# Connectors.net
KiCad netlist of a schematic drawn in Altium Designer
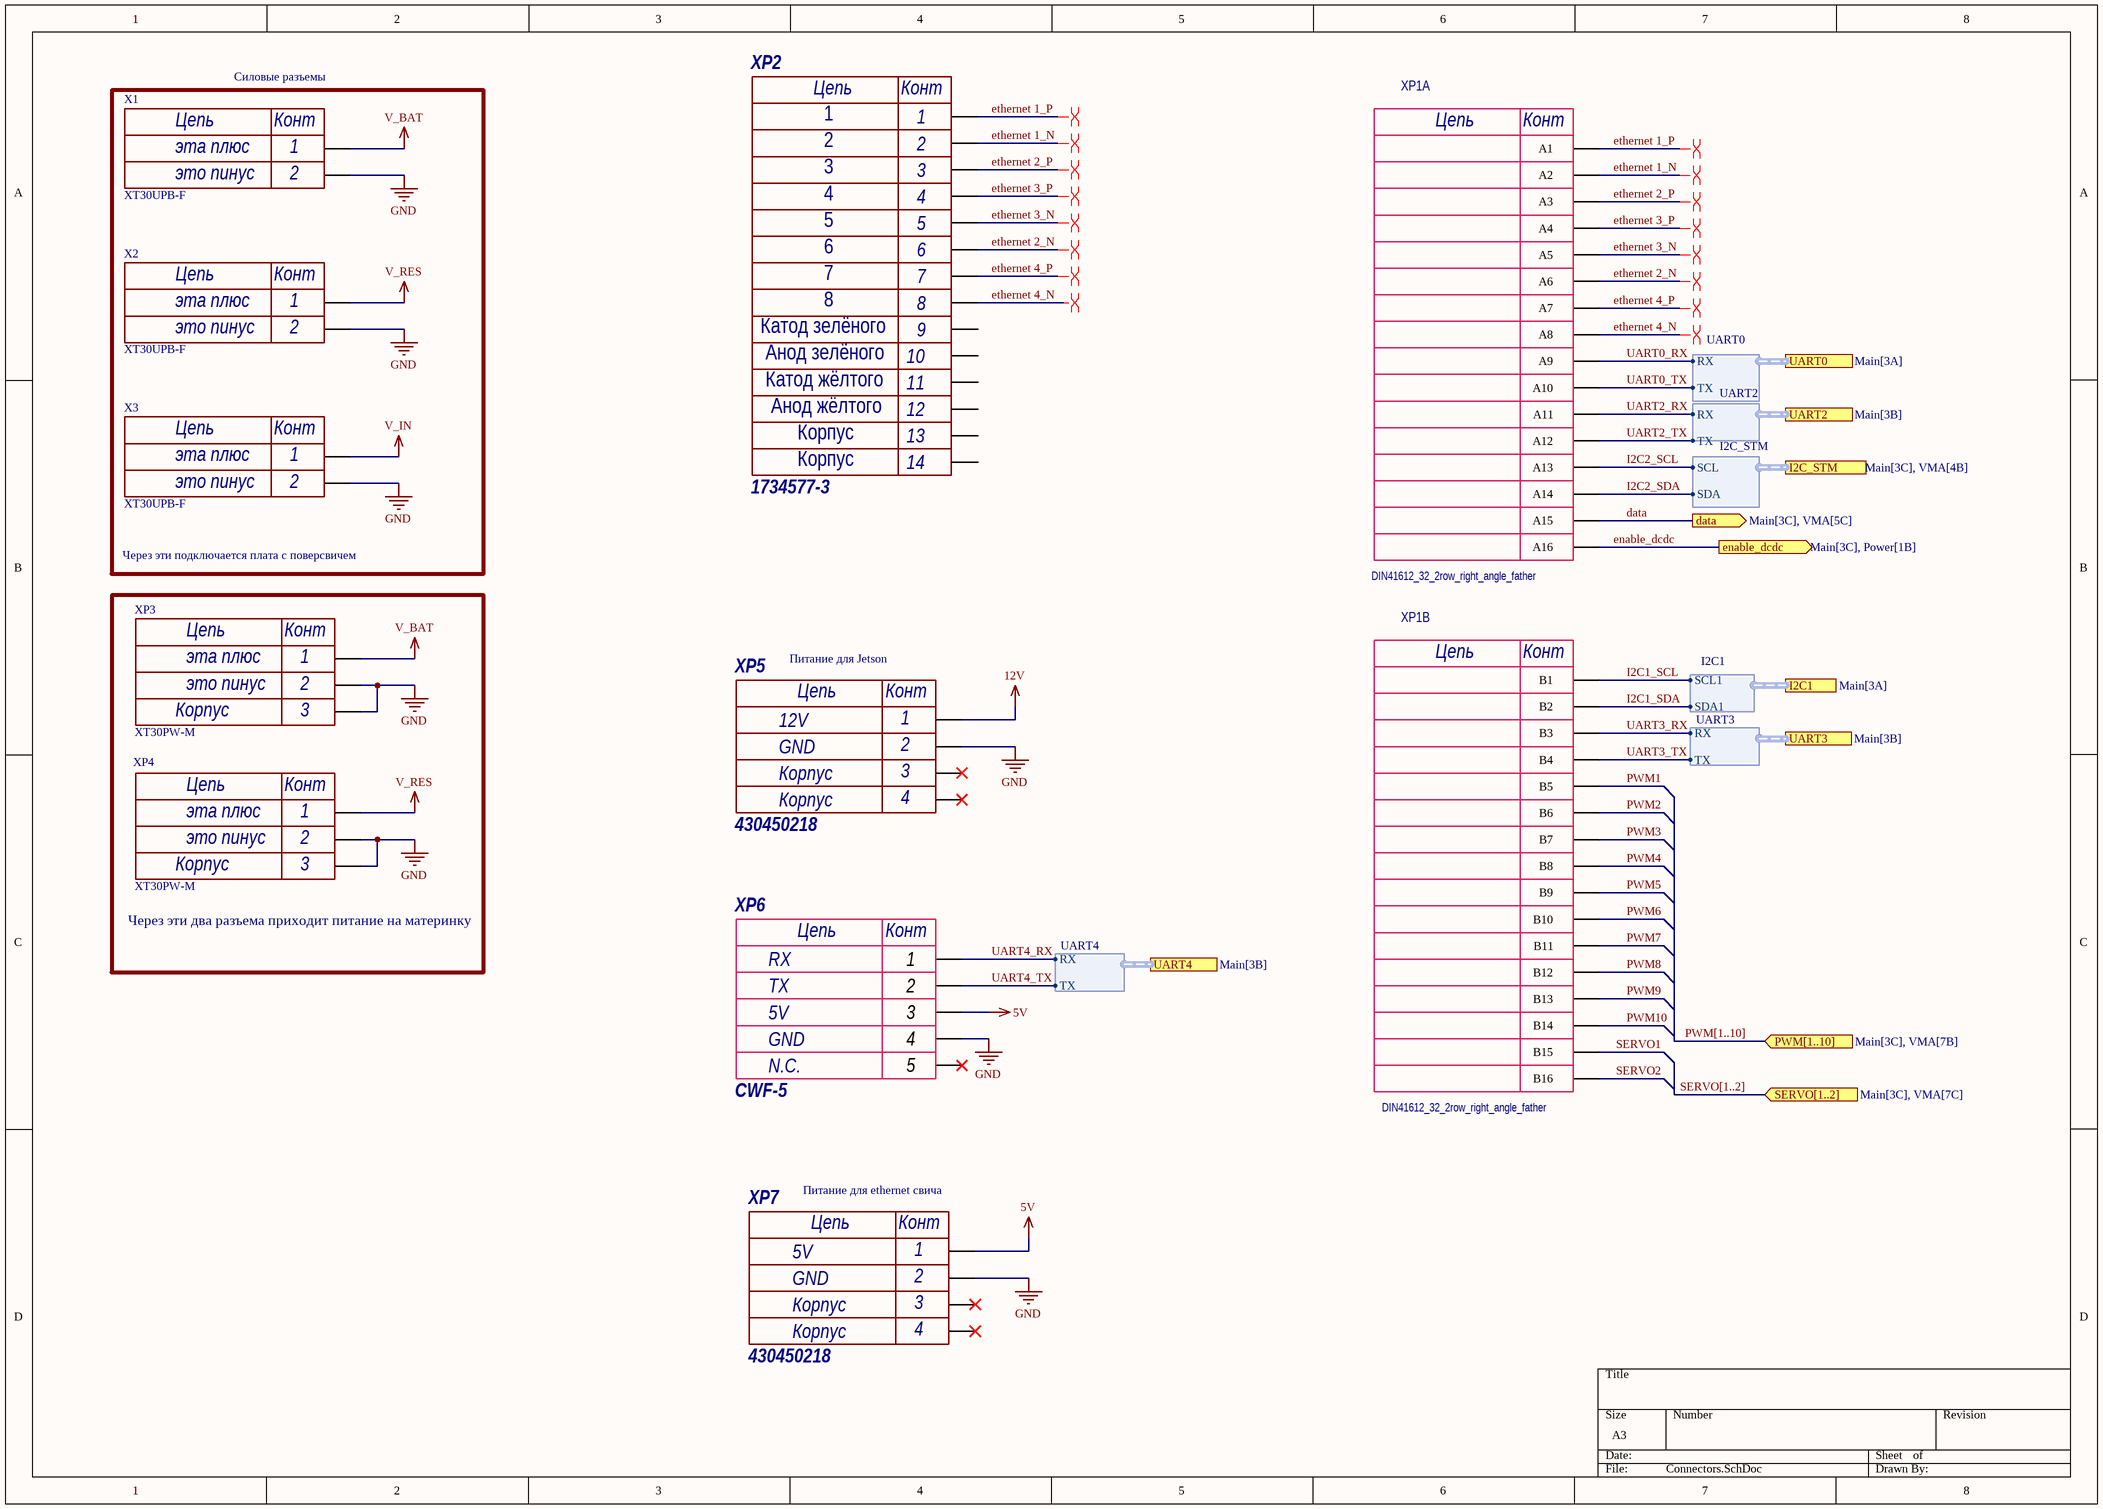
[diagram p0: Connectors.SchDoc]

(export (version "E")
  (design (tool "Eeschema 10.0.6"))
  (components
    (comp (ref "X1")
      (value "XT30UPB-F")
      (footprint "XT30UPB-F")
      (description "30 А (15 продолжительно), прямая мать")
      (fields (field (name "VALUE2") "это пинус") (field (name "VALUE1") "эта плюс"))
      (libsource (lib "Hydrolib") (part "Polar_Conn"))
    )
    (comp (ref "X2")
      (value "XT30UPB-F")
      (footprint "XT30UPB-F")
      (description "30 А (15 продолжительно), прямая мать")
      (fields (field (name "VALUE2") "это пинус") (field (name "VALUE1") "эта плюс"))
      (libsource (lib "Hydrolib") (part "Polar_Conn"))
    )
    (comp (ref "X3")
      (value "XT30UPB-F")
      (footprint "XT30UPB-F")
      (description "30 А (15 продолжительно), прямая мать")
      (fields (field (name "VALUE2") "это пинус") (field (name "VALUE1") "эта плюс"))
      (libsource (lib "Hydrolib") (part "Polar_Conn"))
    )
    (comp (ref "XP1")
      (value "DIN41612_32_2row_right_angle_father")
      (footprint "DIN41612_32_2row_right_angle_father")
      (libsource (lib "") (part "DIN41612_32_2row_1"))
    )
    (comp (ref "XP2")
      (value "1734577-3")
      (footprint "1-1734577-3-rj45-8p8c")
      (description "Модульный разъем, Cat3, RJ45, Гнездо, 8 контакт(-ов), 8 вывод(-ов), 1 порт(-ов)")
      (fields (field (name "PART NUMBER") "1-1734577-3-rj45-8p8c"))
      (libsource (lib "Hydrolib") (part "1-1734577-3-rj45-8p8c"))
    )
    (comp (ref "XP3")
      (value "XT30PW-M")
      (footprint "XT30PW-M")
      (description "30 А (15 продолжительно), 2 контакта разъем угловой отец")
      (fields
        (field (name "VALUE3") "Корпус")
        (field (name "VALUE2") "это пинус")
        (field (name "VALUE1") "эта плюс")
      )
      (libsource (lib "Hydrolib") (part "Polar_Conn_Shield"))
    )
    (comp (ref "XP4")
      (value "XT30PW-M")
      (footprint "XT30PW-M")
      (description "30 А (15 продолжительно), 2 контакта разъем угловой отец")
      (fields
        (field (name "VALUE3") "Корпус")
        (field (name "VALUE2") "это пинус")
        (field (name "VALUE1") "эта плюс")
      )
      (libsource (lib "Hydrolib") (part "Polar_Conn_Shield"))
    )
    (comp (ref "XP5")
      (value "430450218")
      (footprint "Molex_430450218")
      (fields
        (field (name "VALUE3") "Корпус")
        (field (name "VALUE2") "GND")
        (field (name "VALUE4") "Корпус")
        (field (name "VALUE1") "12V")
        (field (name "PART NUMBER") "Molex_430450218")
        (field (name "PARAMETER 1") "Питание для Jetson")
      )
      (libsource (lib "Hydrolib") (part "Molex_430450218"))
    )
    (comp (ref "XP6")
      (value "CWF-5")
      (footprint "CWF-5")
      (description "5-пиновый разъем с ключом")
      (fields
        (field (name "VALUE1") "RX")
        (field (name "VALUE2") "TX")
        (field (name "VALUE3") "5V")
        (field (name "VALUE4") "GND")
        (field (name "VALUE5") "N.C.")
      )
      (libsource (lib "Hydrolib") (part "Conn_5pin"))
    )
    (comp (ref "XP7")
      (value "430450218")
      (footprint "Molex_430450218")
      (fields
        (field (name "VALUE3") "Корпус")
        (field (name "VALUE2") "GND")
        (field (name "VALUE4") "Корпус")
        (field (name "VALUE1") "5V")
        (field (name "PART NUMBER") "Molex_430450218")
        (field (name "PARAMETER 1") "Питание для ethernet свича")
      )
      (libsource (lib "Hydrolib") (part "Molex_430450218"))
    )
  )
  (nets
    (net (code "7") (name "/I2C1_SCL") (class "Default")
      (node (ref "XP1") (pin "B1") (pinfunction "B1_B1") (pintype "passive"))
    )
    (net (code "8") (name "/I2C1_SDA") (class "Default")
      (node (ref "XP1") (pin "B2") (pinfunction "B2_B2") (pintype "passive"))
    )
    (net (code "9") (name "/I2C2_SCL") (class "Default")
      (node (ref "XP1") (pin "A13") (pinfunction "A13_A13") (pintype "passive"))
    )
    (net (code "10") (name "/I2C2_SDA") (class "Default")
      (node (ref "XP1") (pin "A14") (pinfunction "A14_A14") (pintype "passive"))
    )
    (net (code "11") (name "/PWM1") (class "Default")
      (node (ref "XP1") (pin "B5") (pinfunction "B5_B5") (pintype "passive"))
    )
    (net (code "12") (name "/PWM2") (class "Default")
      (node (ref "XP1") (pin "B6") (pinfunction "B6_B6") (pintype "passive"))
    )
    (net (code "13") (name "/PWM3") (class "Default")
      (node (ref "XP1") (pin "B7") (pinfunction "B7_B7") (pintype "passive"))
    )
    (net (code "14") (name "/PWM4") (class "Default")
      (node (ref "XP1") (pin "B8") (pinfunction "B8_B8") (pintype "passive"))
    )
    (net (code "15") (name "/PWM5") (class "Default")
      (node (ref "XP1") (pin "B9") (pinfunction "B9_B9") (pintype "passive"))
    )
    (net (code "16") (name "/PWM6") (class "Default")
      (node (ref "XP1") (pin "B10") (pinfunction "B10_B10") (pintype "passive"))
    )
    (net (code "17") (name "/PWM7") (class "Default")
      (node (ref "XP1") (pin "B11") (pinfunction "B11_B11") (pintype "passive"))
    )
    (net (code "18") (name "/PWM8") (class "Default")
      (node (ref "XP1") (pin "B12") (pinfunction "B12_B12") (pintype "passive"))
    )
    (net (code "19") (name "/PWM9") (class "Default")
      (node (ref "XP1") (pin "B13") (pinfunction "B13_B13") (pintype "passive"))
    )
    (net (code "20") (name "/PWM10") (class "Default")
      (node (ref "XP1") (pin "B14") (pinfunction "B14_B14") (pintype "passive"))
    )
    (net (code "22") (name "/SERVO1") (class "Default")
      (node (ref "XP1") (pin "B15") (pinfunction "B15_B15") (pintype "passive"))
    )
    (net (code "23") (name "/SERVO2") (class "Default")
      (node (ref "XP1") (pin "B16") (pinfunction "B16_B16") (pintype "passive"))
    )
    (net (code "25") (name "/UART0_RX") (class "Default")
      (node (ref "XP1") (pin "A9") (pinfunction "A9_A9") (pintype "passive"))
    )
    (net (code "26") (name "/UART0_TX") (class "Default")
      (node (ref "XP1") (pin "A10") (pinfunction "A10_A10") (pintype "passive"))
    )
    (net (code "27") (name "/UART2_RX") (class "Default")
      (node (ref "XP1") (pin "A11") (pinfunction "A11_A11") (pintype "passive"))
    )
    (net (code "28") (name "/UART2_TX") (class "Default")
      (node (ref "XP1") (pin "A12") (pinfunction "A12_A12") (pintype "passive"))
    )
    (net (code "29") (name "/UART3_RX") (class "Default")
      (node (ref "XP1") (pin "B3") (pinfunction "B3_B3") (pintype "passive"))
    )
    (net (code "30") (name "/UART3_TX") (class "Default")
      (node (ref "XP1") (pin "B4") (pinfunction "B4_B4") (pintype "passive"))
    )
    (net (code "31") (name "/UART4_RX") (class "Default")
      (node (ref "XP6") (pin "1") (pinfunction "1_1") (pintype "passive"))
    )
    (net (code "32") (name "/UART4_TX") (class "Default")
      (node (ref "XP6") (pin "2") (pinfunction "2_2") (pintype "passive"))
    )
    (net (code "33") (name "/data") (class "Default")
      (node (ref "XP1") (pin "A15") (pinfunction "A15_A15") (pintype "passive"))
    )
    (net (code "34") (name "/enable_dcdc") (class "Default")
      (node (ref "XP1") (pin "A16") (pinfunction "A16_A16") (pintype "passive"))
    )
    (net (code "35") (name "/ethernet 1_N") (class "Default")
      (node (ref "XP1") (pin "A2") (pinfunction "A2_A2") (pintype "passive"))
      (node (ref "XP2") (pin "2") (pinfunction "2_2") (pintype "passive"))
    )
    (net (code "36") (name "/ethernet 1_P") (class "Default")
      (node (ref "XP1") (pin "A1") (pinfunction "A1_A1") (pintype "passive"))
      (node (ref "XP2") (pin "1") (pinfunction "1_1") (pintype "passive"))
    )
    (net (code "37") (name "/ethernet 2_N") (class "Default")
      (node (ref "XP1") (pin "A6") (pinfunction "A6_A6") (pintype "passive"))
      (node (ref "XP2") (pin "6") (pinfunction "6_6") (pintype "passive"))
    )
    (net (code "38") (name "/ethernet 2_P") (class "Default")
      (node (ref "XP1") (pin "A3") (pinfunction "A3_A3") (pintype "passive"))
      (node (ref "XP2") (pin "3") (pinfunction "3_3") (pintype "passive"))
    )
    (net (code "39") (name "/ethernet 3_N") (class "Default")
      (node (ref "XP1") (pin "A5") (pinfunction "A5_A5") (pintype "passive"))
      (node (ref "XP2") (pin "5") (pinfunction "5_5") (pintype "passive"))
    )
    (net (code "40") (name "/ethernet 3_P") (class "Default")
      (node (ref "XP1") (pin "A4") (pinfunction "A4_A4") (pintype "passive"))
      (node (ref "XP2") (pin "4") (pinfunction "4_4") (pintype "passive"))
    )
    (net (code "41") (name "/ethernet 4_N") (class "Default")
      (node (ref "XP1") (pin "A8") (pinfunction "A8_A8") (pintype "passive"))
      (node (ref "XP2") (pin "8") (pinfunction "8_8") (pintype "passive"))
    )
    (net (code "42") (name "/ethernet 4_P") (class "Default")
      (node (ref "XP1") (pin "A7") (pinfunction "A7_A7") (pintype "passive"))
      (node (ref "XP2") (pin "7") (pinfunction "7_7") (pintype "passive"))
    )
    (net (code "49") (name "5V") (class "Default")
      (node (ref "XP6") (pin "3") (pinfunction "3_3") (pintype "passive"))
      (node (ref "XP7") (pin "1") (pinfunction "1_1") (pintype "passive"))
    )
    (net (code "50") (name "12V") (class "Default")
      (node (ref "XP5") (pin "1") (pinfunction "1_1") (pintype "passive"))
    )
    (net (code "51") (name "GND") (class "Default")
      (node (ref "X1") (pin "N") (pinfunction "N_N") (pintype "passive"))
      (node (ref "X2") (pin "N") (pinfunction "N_N") (pintype "passive"))
      (node (ref "X3") (pin "N") (pinfunction "N_N") (pintype "passive"))
      (node (ref "XP3") (pin "0") (pinfunction "0_0") (pintype "passive"))
      (node (ref "XP3") (pin "N") (pinfunction "N_N") (pintype "passive"))
      (node (ref "XP4") (pin "0") (pinfunction "0_0") (pintype "passive"))
      (node (ref "XP4") (pin "N") (pinfunction "N_N") (pintype "passive"))
      (node (ref "XP5") (pin "2") (pinfunction "2_2") (pintype "passive"))
      (node (ref "XP6") (pin "4") (pinfunction "4_4") (pintype "passive"))
      (node (ref "XP7") (pin "2") (pinfunction "2_2") (pintype "passive"))
    )
    (net (code "52") (name "V_BAT") (class "Default")
      (node (ref "X1") (pin "P") (pinfunction "P_P") (pintype "passive"))
      (node (ref "XP3") (pin "P") (pinfunction "P_P") (pintype "passive"))
    )
    (net (code "53") (name "V_IN") (class "Default")
      (node (ref "X3") (pin "P") (pinfunction "P_P") (pintype "passive"))
    )
    (net (code "54") (name "V_RES") (class "Default")
      (node (ref "X2") (pin "P") (pinfunction "P_P") (pintype "passive"))
      (node (ref "XP4") (pin "P") (pinfunction "P_P") (pintype "passive"))
    )
    (net (code "55") (name "unconnected-(XP2-Pad9)") (class "Default")
      (node (ref "XP2") (pin "9") (pinfunction "9_9") (pintype "passive"))
    )
    (net (code "56") (name "unconnected-(XP2-Pad10)") (class "Default")
      (node (ref "XP2") (pin "10") (pinfunction "10_10") (pintype "passive"))
    )
    (net (code "57") (name "unconnected-(XP2-Pad11)") (class "Default")
      (node (ref "XP2") (pin "11") (pinfunction "11_11") (pintype "passive"))
    )
    (net (code "58") (name "unconnected-(XP2-Pad12)") (class "Default")
      (node (ref "XP2") (pin "12") (pinfunction "12_12") (pintype "passive"))
    )
    (net (code "59") (name "unconnected-(XP2-PadMH1)") (class "Default")
      (node (ref "XP2") (pin "MH1") (pinfunction "MH1_MH1") (pintype "passive"))
    )
    (net (code "60") (name "unconnected-(XP2-PadMH2)") (class "Default")
      (node (ref "XP2") (pin "MH2") (pinfunction "MH2_MH2") (pintype "passive"))
    )
    (net (code "61") (name "unconnected-(XP5-Pad0)") (class "Default")
      (node (ref "XP5") (pin "0") (pinfunction "0_0") (pintype "passive+no_connect"))
    )
    (net (code "62") (name "unconnected-(XP5-Pad0)_1") (class "Default")
      (node (ref "XP5") (pin "0") (pinfunction "0_0") (pintype "passive+no_connect"))
    )
    (net (code "63") (name "unconnected-(XP6-Pad5)") (class "Default")
      (node (ref "XP6") (pin "5") (pinfunction "5_5") (pintype "passive+no_connect"))
    )
    (net (code "64") (name "unconnected-(XP7-Pad0)") (class "Default")
      (node (ref "XP7") (pin "0") (pinfunction "0_0") (pintype "passive+no_connect"))
    )
    (net (code "65") (name "unconnected-(XP7-Pad0)_1") (class "Default")
      (node (ref "XP7") (pin "0") (pinfunction "0_0") (pintype "passive+no_connect"))
    )
  )
)
